# ResetCkt.net
KiCad netlist of a schematic drawn in Altium Designer
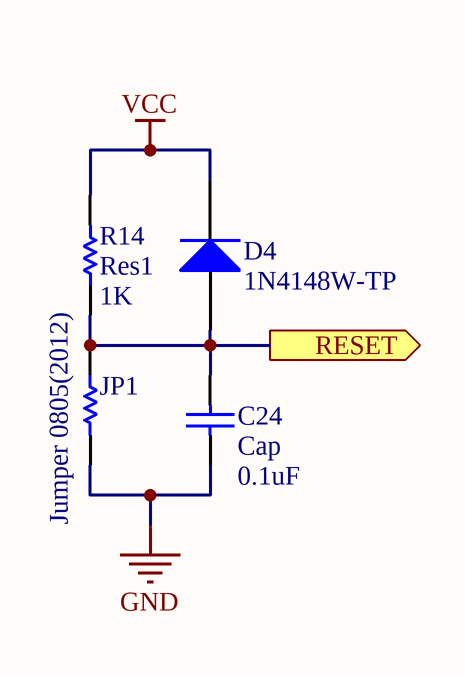
[diagram p0: ResetCkt.SchDoc]

(export (version "E")
  (design (tool "Eeschema 10.0.6"))
  (components
    (comp (ref "C24")
      (value "Cap")
      (footprint "C0805")
      (description "Capacitor")
      (fields (field (name "ALTIUM_VALUE") "0.1uF") (field (name "PUBLISHER") "Altium Limited"))
      (libsource (lib "Miscellaneous Devices") (part "Cap"))
    )
    (comp (ref "D4")
      (value "1N4148W-TP")
      (footprint "MCC-SOD123_V")
      (description "High Speed Switching Diode, 400 mW, 150 mA, -65 to 150 degC, 2-Pin SOD123, RoHS, Tape and Reel")
      (fields (field (name "MANUFACTURER") "Micro Commercial Components"))
      (libsource (lib "Altium Content Vault") (part "D-AK-2"))
    )
    (comp (ref "JP1")
      (value "Jumper 0805(2012)")
      (footprint "RESC0805(2012)_N")
      (description "Jumper 0805 (2012 Metric)")
      (fields (field (name "TOLERANCE") "None"))
      (libsource (lib "Altium Content Vault") (part "RES"))
    )
    (comp (ref "R14")
      (value "Res1")
      (footprint "6-0805_L")
      (description "Resistor")
      (fields (field (name "ALTIUM_VALUE") "1K") (field (name "PUBLISHER") "Altium Limited"))
      (libsource (lib "Miscellaneous Devices") (part "Res1"))
    )
  )
  (nets
    (net (code "1") (name "/RESET") (class "Default")
      (node (ref "C24") (pin "2") (pinfunction "2_2") (pintype "passive"))
      (node (ref "D4") (pin "1") (pinfunction "A_1") (pintype "passive"))
      (node (ref "JP1") (pin "1") (pinfunction "1_1") (pintype "passive"))
      (node (ref "R14") (pin "1") (pinfunction "1_1") (pintype "passive"))
    )
    (net (code "2") (name "GND") (class "Default")
      (node (ref "C24") (pin "1") (pinfunction "1_1") (pintype "passive"))
      (node (ref "JP1") (pin "2") (pinfunction "2_2") (pintype "passive"))
    )
    (net (code "3") (name "VCC") (class "Default")
      (node (ref "D4") (pin "2") (pinfunction "K_2") (pintype "passive"))
      (node (ref "R14") (pin "2") (pinfunction "2_2") (pintype "passive"))
    )
  )
)
